# LIDO-HW_300_StatusLightInterface.net
KiCad netlist of a schematic drawn in Altium Designer
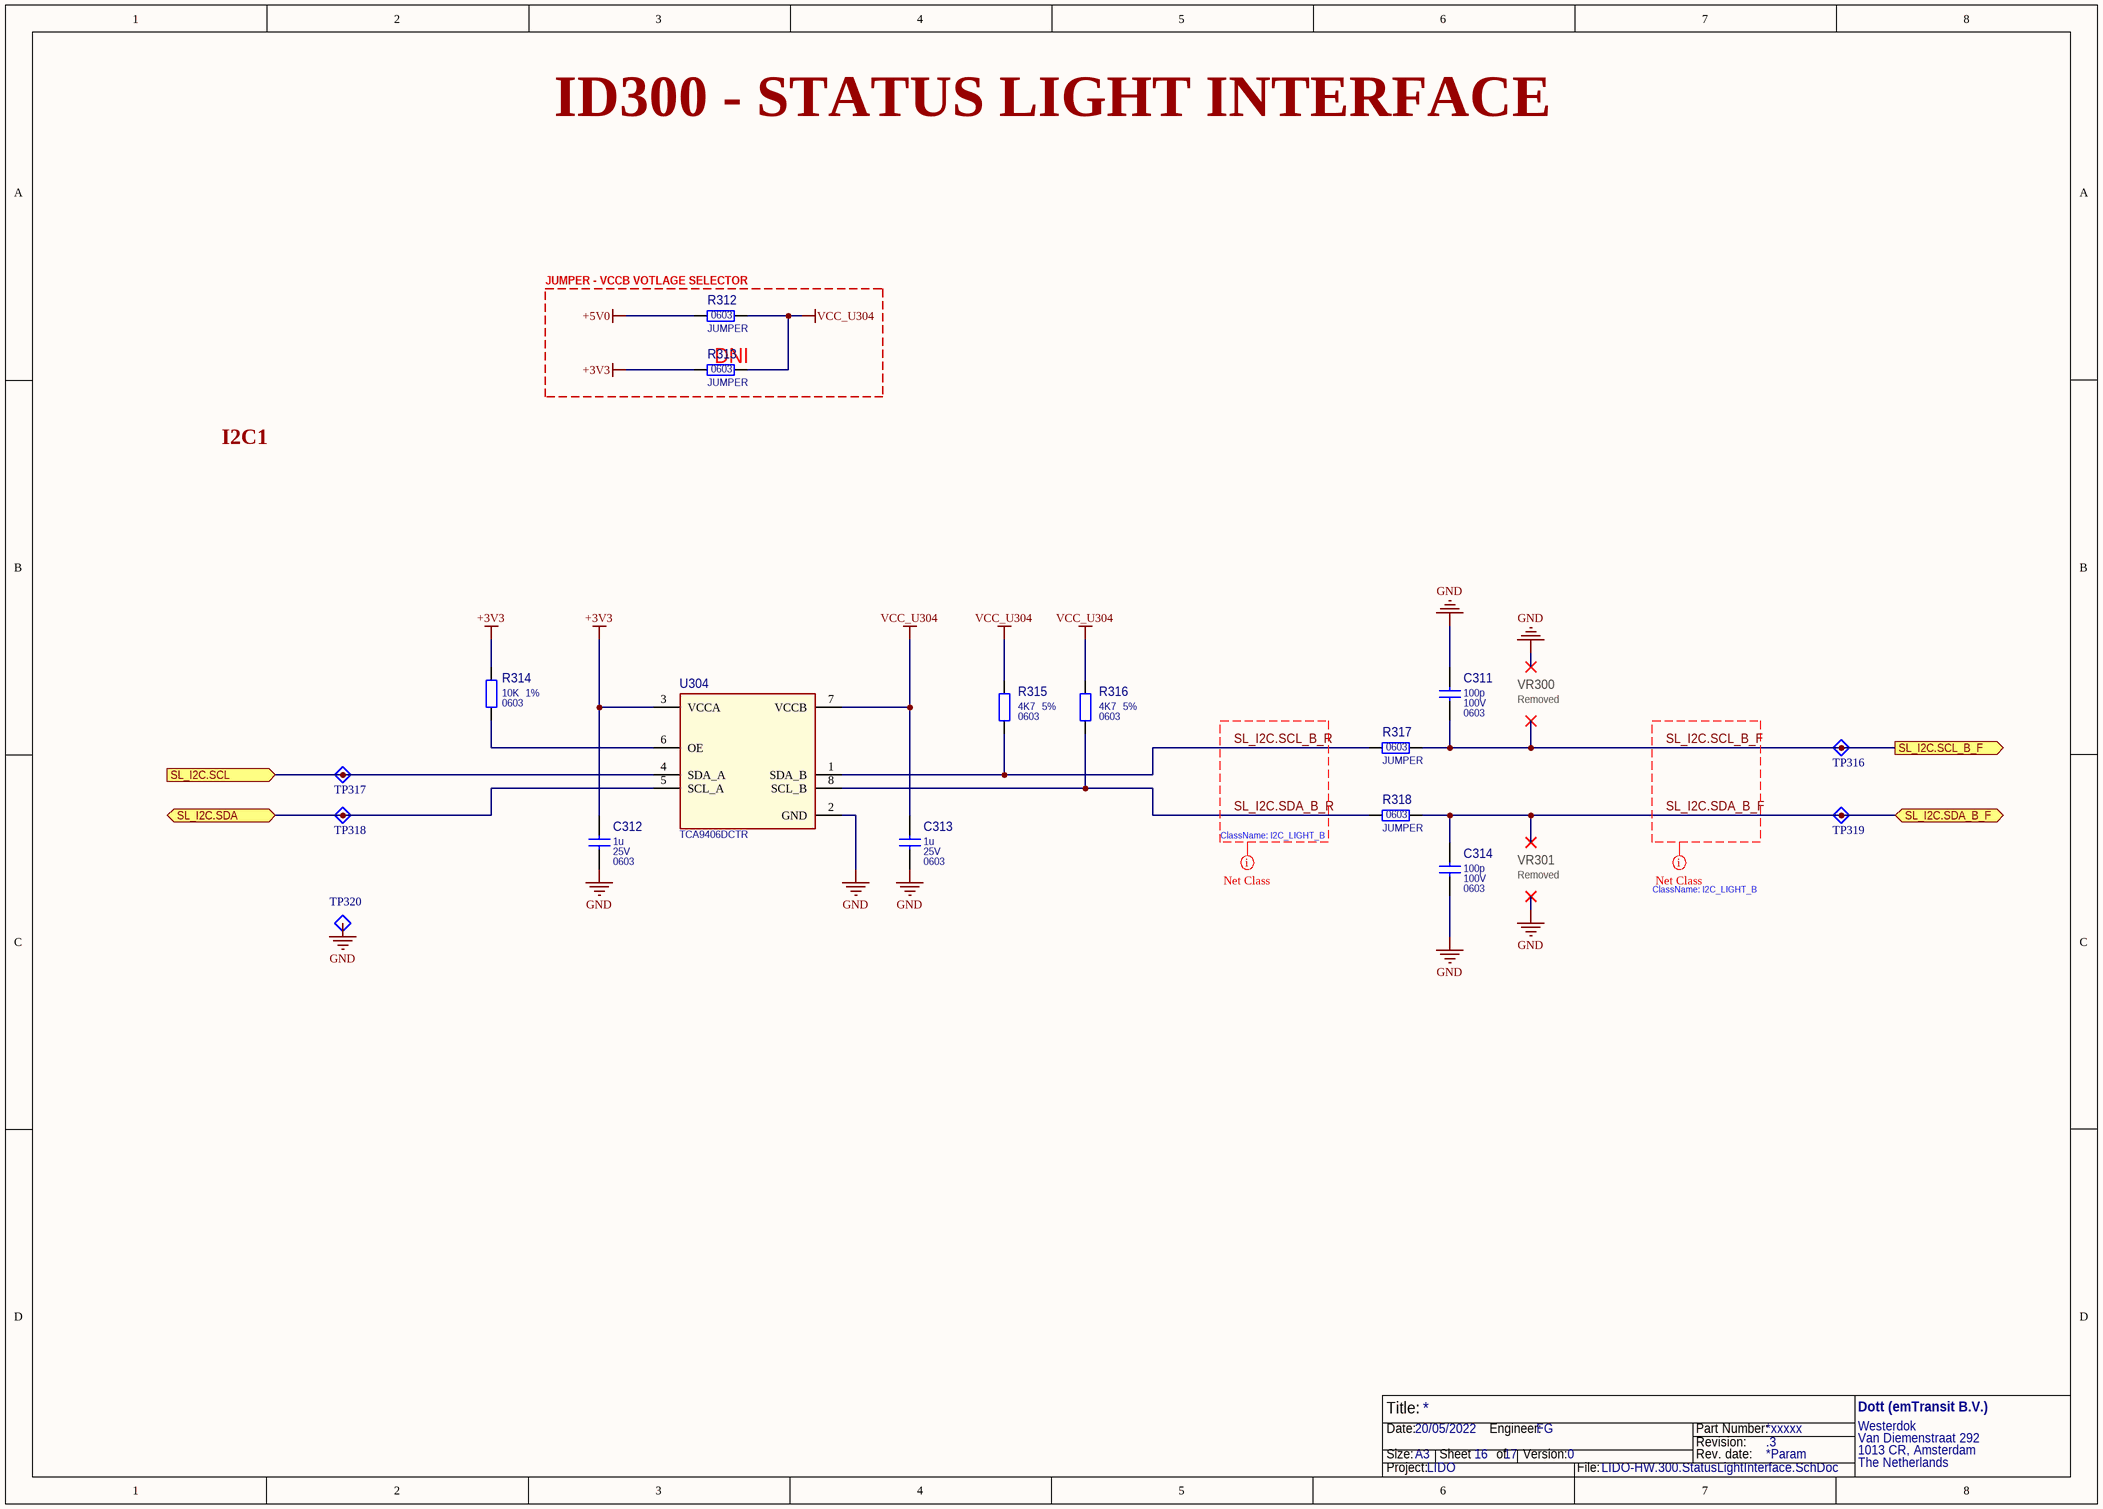
[diagram p0: LIDO-HW.300.StatusLightInterface.SchDoc]

(export (version "E")
  (design (tool "Eeschema 10.0.6"))
  (components
    (comp (ref "C311")
      (value "100p")
      (footprint "CAP_0603_1608X90-N_MURATA_A")
      (description "CAP CER 100PF 100V C0G 0603")
      (fields
        (field (name "MANUFACTURER PART NUMBER") "CGA3E2C0G2A101J080AA")
        (field (name "MANUFACTURER") "TDK Corporation")
        (field (name "PART VALUE 2") "100V")
        (field (name "PART PACKAGE") "0603")
      )
      (libsource (lib "DB_Library") (part "Ceramic"))
    )
    (comp (ref "C312")
      (value "1u")
      (footprint "CAP_0603_1608X90-N_MURATA_A")
      (description "CAP CER 1UF 25V X7R 0603")
      (fields
        (field (name "MANUFACTURER PART NUMBER") "CGA3E1X7R1E105M080AE")
        (field (name "MANUFACTURER") "TDK Corporation")
        (field (name "PART VALUE 2") "25V")
        (field (name "PART PACKAGE") "0603")
      )
      (libsource (lib "DB_Library") (part "Ceramic"))
    )
    (comp (ref "C313")
      (value "1u")
      (footprint "CAP_0603_1608X90-N_MURATA_A")
      (description "CAP CER 1UF 25V X7R 0603")
      (fields
        (field (name "MANUFACTURER PART NUMBER") "CGA3E1X7R1E105M080AE")
        (field (name "MANUFACTURER") "TDK Corporation")
        (field (name "PART VALUE 2") "25V")
        (field (name "PART PACKAGE") "0603")
      )
      (libsource (lib "DB_Library") (part "Ceramic"))
    )
    (comp (ref "C314")
      (value "100p")
      (footprint "CAP_0603_1608X90-N_MURATA_A")
      (description "CAP CER 100PF 100V C0G 0603")
      (fields
        (field (name "MANUFACTURER PART NUMBER") "CGA3E2C0G2A101J080AA")
        (field (name "MANUFACTURER") "TDK Corporation")
        (field (name "PART VALUE 2") "100V")
        (field (name "PART PACKAGE") "0603")
      )
      (libsource (lib "DB_Library") (part "Ceramic"))
    )
    (comp (ref "R312")
      (value "JUMPER")
      (footprint "RES_0603_1608X60-N_YAGEO_A")
      (description "RES 0 OHM JUMPER 1/10W 0603")
      (fields
        (field (name "MANUFACTURER PART NUMBER") "RC0603JR-070RL")
        (field (name "MANUFACTURER") "YAGEO")
        (field (name "PART PACKAGE") "0603")
      )
      (libsource (lib "") (part "Resistor_1"))
    )
    (comp (ref "R313")
      (value "JUMPER")
      (footprint "RES_0603_1608X60-N_YAGEO_A")
      (description "RES 0 OHM JUMPER 1/10W 0603")
      (fields
        (field (name "MANUFACTURER PART NUMBER") "RC0603JR-070RL")
        (field (name "MANUFACTURER") "YAGEO")
        (field (name "PART PACKAGE") "0603")
      )
      (libsource (lib "") (part "Resistor_1"))
    )
    (comp (ref "R314")
      (value "10K")
      (footprint "RES_0603_1608X60-N_YAGEO_A")
      (description "RES 10K OHM 1% 1/10W 0603")
      (fields
        (field (name "MANUFACTURER PART NUMBER") "RC0603FR-0710KL")
        (field (name "MANUFACTURER") "YAGEO")
        (field (name "PART VALUE 2") "1%")
        (field (name "PART PACKAGE") "0603")
      )
      (libsource (lib "DB_Library") (part "Resistor"))
    )
    (comp (ref "R315")
      (value "4K7")
      (footprint "RES_0603_1608X60-N_YAGEO_A")
      (description "RES 4.7K OHM 5% 1/10W 0603")
      (fields
        (field (name "MANUFACTURER PART NUMBER") "RC0603JR-074K7L")
        (field (name "MANUFACTURER") "YAGEO")
        (field (name "PART VALUE 2") "5%")
        (field (name "PART PACKAGE") "0603")
      )
      (libsource (lib "DB_Library") (part "Resistor"))
    )
    (comp (ref "R316")
      (value "4K7")
      (footprint "RES_0603_1608X60-N_YAGEO_A")
      (description "RES 4.7K OHM 5% 1/10W 0603")
      (fields
        (field (name "MANUFACTURER PART NUMBER") "RC0603JR-074K7L")
        (field (name "MANUFACTURER") "YAGEO")
        (field (name "PART VALUE 2") "5%")
        (field (name "PART PACKAGE") "0603")
      )
      (libsource (lib "DB_Library") (part "Resistor"))
    )
    (comp (ref "R317")
      (value "JUMPER")
      (footprint "RES_0603_1608X60-N_YAGEO_A")
      (description "RES 0 OHM JUMPER 1/10W 0603")
      (fields
        (field (name "MANUFACTURER PART NUMBER") "RC0603JR-070RL")
        (field (name "MANUFACTURER") "YAGEO")
        (field (name "PART PACKAGE") "0603")
      )
      (libsource (lib "") (part "Resistor_1"))
    )
    (comp (ref "R318")
      (value "JUMPER")
      (footprint "RES_0603_1608X60-N_YAGEO_A")
      (description "RES 0 OHM JUMPER 1/10W 0603")
      (fields
        (field (name "MANUFACTURER PART NUMBER") "RC0603JR-070RL")
        (field (name "MANUFACTURER") "YAGEO")
        (field (name "PART PACKAGE") "0603")
      )
      (libsource (lib "") (part "Resistor_1"))
    )
    (comp (ref "TP316")
      (value "TestPoint_A")
      (footprint "TESTPOINT_1D_A")
      (description "Pad Diamater 1mm")
      (fields (field (name "PART") "Test Point 1D A") (field (name "OBSOLETE PART") "False"))
      (libsource (lib "DB_Library") (part "TestPoint_A"))
    )
    (comp (ref "TP317")
      (value "TestPoint_A")
      (footprint "TESTPOINT_1D_A")
      (description "Pad Diamater 1mm")
      (fields (field (name "PART") "Test Point 1D A") (field (name "OBSOLETE PART") "False"))
      (libsource (lib "DB_Library") (part "TestPoint_A"))
    )
    (comp (ref "TP318")
      (value "TestPoint_A")
      (footprint "TESTPOINT_1D_A")
      (description "Pad Diamater 1mm")
      (fields (field (name "PART") "Test Point 1D A") (field (name "OBSOLETE PART") "False"))
      (libsource (lib "DB_Library") (part "TestPoint_A"))
    )
    (comp (ref "TP319")
      (value "TestPoint_A")
      (footprint "TESTPOINT_1D_A")
      (description "Pad Diamater 1mm")
      (fields (field (name "PART") "Test Point 1D A") (field (name "OBSOLETE PART") "False"))
      (libsource (lib "DB_Library") (part "TestPoint_A"))
    )
    (comp (ref "TP320")
      (value "TestPoint_A")
      (footprint "TESTPOINT_1D_A")
      (description "Pad Diamater 1mm")
      (fields (field (name "PART") "Test Point 1D A") (field (name "OBSOLETE PART") "False"))
      (libsource (lib "DB_Library") (part "TestPoint_A"))
    )
    (comp (ref "U304")
      (value "TCA9406DCTR")
      (footprint "SSOP8P65_295X400X130L40X25-N_TI_A")
      (description "Voltage Level Translator Bidirectional 1 Circuit 2 Channel 24Mbps SM8")
      (fields (field (name "MANUFACTURER") "Texas Instruments") (field (name "OBSOLETE PART") "False"))
      (libsource (lib "DB_Library") (part "TCA9406_A"))
    )
  )
  (nets
    (net (code "1") (name "+3V3") (class "Default")
      (node (ref "C312") (pin "1") (pinfunction "1_1") (pintype "passive"))
      (node (ref "R313") (pin "1") (pinfunction "1_1") (pintype "passive"))
      (node (ref "R314") (pin "2") (pinfunction "2_2") (pintype "passive"))
      (node (ref "U304") (pin "3") (pinfunction "VCCA_3") (pintype "power_in"))
    )
    (net (code "2") (name "+5V0") (class "Default")
      (node (ref "R312") (pin "1") (pinfunction "1_1") (pintype "passive"))
    )
    (net (code "3") (name "/SL_I2C.SCL") (class "Default")
      (node (ref "TP317") (pin "1") (pinfunction "TP_1") (pintype "passive"))
      (node (ref "U304") (pin "4") (pinfunction "SDA_A_4") (pintype "passive"))
    )
    (net (code "4") (name "/SL_I2C.SCL_B_F") (class "Default")
      (node (ref "C311") (pin "2") (pinfunction "2_2") (pintype "passive"))
      (node (ref "R317") (pin "2") (pinfunction "2_2") (pintype "passive"))
      (node (ref "TP316") (pin "1") (pinfunction "TP_1") (pintype "passive"))
    )
    (net (code "5") (name "/SL_I2C.SCL_B_R") (class "Default")
      (node (ref "R315") (pin "1") (pinfunction "1_1") (pintype "passive"))
      (node (ref "R317") (pin "1") (pinfunction "1_1") (pintype "passive"))
      (node (ref "U304") (pin "1") (pinfunction "SDA_B_1") (pintype "passive"))
    )
    (net (code "6") (name "/SL_I2C.SDA") (class "Default")
      (node (ref "TP318") (pin "1") (pinfunction "TP_1") (pintype "passive"))
      (node (ref "U304") (pin "5") (pinfunction "SCL_A_5") (pintype "passive"))
    )
    (net (code "7") (name "/SL_I2C.SDA_B_F") (class "Default")
      (node (ref "C314") (pin "1") (pinfunction "1_1") (pintype "passive"))
      (node (ref "R318") (pin "2") (pinfunction "2_2") (pintype "passive"))
      (node (ref "TP319") (pin "1") (pinfunction "TP_1") (pintype "passive"))
    )
    (net (code "8") (name "/SL_I2C.SDA_B_R") (class "Default")
      (node (ref "R316") (pin "1") (pinfunction "1_1") (pintype "passive"))
      (node (ref "R318") (pin "1") (pinfunction "1_1") (pintype "passive"))
      (node (ref "U304") (pin "8") (pinfunction "SCL_B_8") (pintype "passive"))
    )
    (net (code "9") (name "GND") (class "Default")
      (node (ref "C311") (pin "1") (pinfunction "1_1") (pintype "passive"))
      (node (ref "C312") (pin "2") (pinfunction "2_2") (pintype "passive"))
      (node (ref "C313") (pin "2") (pinfunction "2_2") (pintype "passive"))
      (node (ref "C314") (pin "2") (pinfunction "2_2") (pintype "passive"))
      (node (ref "TP320") (pin "1") (pinfunction "TP_1") (pintype "passive"))
      (node (ref "U304") (pin "2") (pinfunction "GND_2") (pintype "power_in"))
    )
    (net (code "10") (name "Net-(U304-OE)") (class "Default")
      (node (ref "R314") (pin "1") (pinfunction "1_1") (pintype "passive"))
      (node (ref "U304") (pin "6") (pinfunction "OE_6") (pintype "passive"))
    )
    (net (code "11") (name "VCC_U304") (class "Default")
      (node (ref "C313") (pin "1") (pinfunction "1_1") (pintype "passive"))
      (node (ref "R312") (pin "2") (pinfunction "2_2") (pintype "passive"))
      (node (ref "R313") (pin "2") (pinfunction "2_2") (pintype "passive"))
      (node (ref "R315") (pin "2") (pinfunction "2_2") (pintype "passive"))
      (node (ref "R316") (pin "2") (pinfunction "2_2") (pintype "passive"))
      (node (ref "U304") (pin "7") (pinfunction "VCCB_7") (pintype "power_in"))
    )
  )
)
